# MSP430.net
KiCad netlist of a schematic drawn in Altium Designer
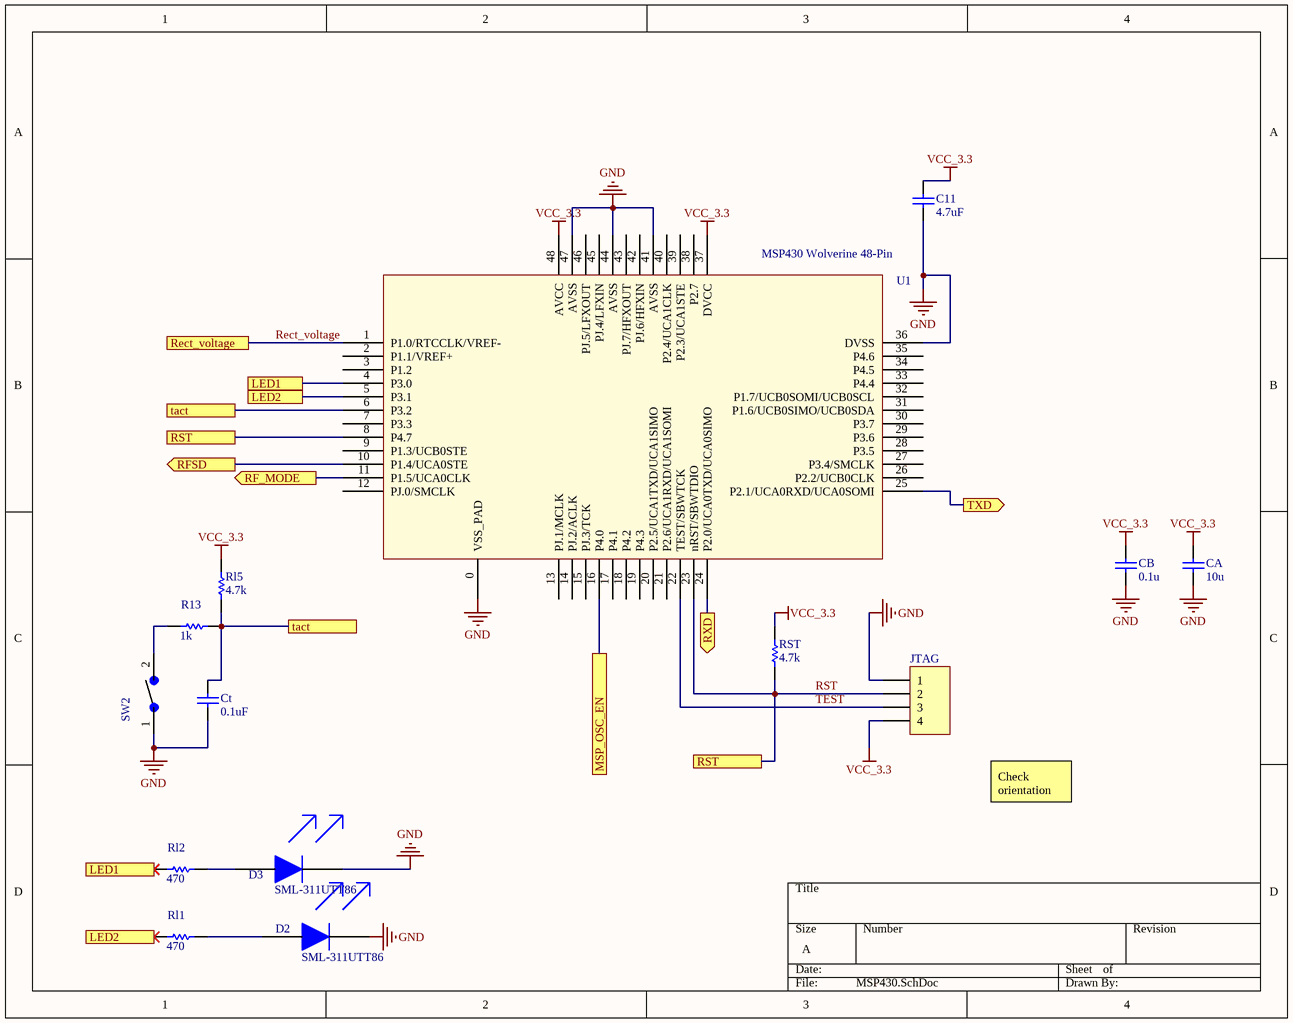
[diagram p0: MSP430.SchDoc]

(export (version "E")
  (design (tool "Eeschema 10.0.6"))
  (components
    (comp (ref "C11")
      (value "4.7uF")
      (footprint "0402-W")
      (description "Ceramic Capacitor (Surface Mount)")
      (fields (field (name "MANUFACTURER") "Generic Ceramic Chip Cap (TBD)") (field (name "Comment") "Cap"))
      (libsource (lib "WISP_AD10") (part "Cap"))
    )
    (comp (ref "CA")
      (value "10u")
      (footprint "0402-W")
      (description "Ceramic Capacitor (Surface Mount)")
      (fields (field (name "MANUFACTURER") "Generic Ceramic Chip Cap (TBD)") (field (name "Comment") "Cap"))
      (libsource (lib "wisp") (part "Cap"))
    )
    (comp (ref "CB")
      (value "0.1u")
      (footprint "0402-W")
      (description "Ceramic Capacitor (Surface Mount)")
      (fields (field (name "MANUFACTURER") "Generic Ceramic Chip Cap (TBD)") (field (name "Comment") "Cap"))
      (libsource (lib "wisp") (part "Cap"))
    )
    (comp (ref "Ct")
      (value "0.1uF")
      (footprint "0402-W")
      (description "Ceramic Capacitor (Surface Mount)")
      (fields (field (name "MANUFACTURER") "Generic Ceramic Chip Cap (TBD)") (field (name "Comment") "Cap"))
      (libsource (lib "WISP_AD10") (part "Cap"))
    )
    (comp (ref "D2")
      (value "SML-311UTT86")
      (footprint "0603")
      (description "LED 630NM RED WTR CLR 0603 SMD")
      (libsource (lib "Fromm") (part "SML-311UTT86"))
    )
    (comp (ref "D3")
      (value "SML-311UTT86")
      (footprint "0603")
      (description "LED 630NM RED WTR CLR 0603 SMD")
      (libsource (lib "Fromm") (part "SML-311UTT86"))
    )
    (comp (ref "JTAG")
      (value "MHDR1X4")
      (footprint "MHDR1X4")
      (description "Header, 4-Pin")
      (fields (field (name "PUBLISHER") "Altium Limited"))
      (libsource (lib "Miscellaneous Connectors") (part "MHDR1X4"))
    )
    (comp (ref "R13")
      (value "1k")
      (footprint "0402")
      (description "Chip Resistor (Surface Mount)")
      (fields (field (name "MANUFACTURER") "Generic Chip Res (TBD)") (field (name "Comment") "Res"))
      (libsource (lib "wisp") (part "Res"))
    )
    (comp (ref "Rl1")
      (value "470")
      (footprint "0402")
      (description "Chip Resistor (Surface Mount)")
      (fields (field (name "MANUFACTURER") "Generic Chip Res (TBD)") (field (name "Comment") "Res"))
      (libsource (lib "wisp") (part "Res"))
    )
    (comp (ref "Rl2")
      (value "470")
      (footprint "0402")
      (description "Chip Resistor (Surface Mount)")
      (fields (field (name "MANUFACTURER") "Generic Chip Res (TBD)") (field (name "Comment") "Res"))
      (libsource (lib "wisp") (part "Res"))
    )
    (comp (ref "Rl5")
      (value "4.7k")
      (footprint "0402")
      (description "Chip Resistor (Surface Mount)")
      (fields (field (name "MANUFACTURER") "Generic Chip Res (TBD)") (field (name "Comment") "Res"))
      (libsource (lib "wisp") (part "Res"))
    )
    (comp (ref "RST")
      (value "Res")
      (footprint "0402")
      (description "Chip Resistor (Surface Mount)")
      (fields (field (name "MANUFACTURER") "Generic Chip Res (TBD)") (field (name "RST") "4.7k"))
      (libsource (lib "wisp") (part "Res"))
    )
    (comp (ref "SW2")
      (value "FSMSM _1437566-3_")
      (footprint "TE_FSMSM")
      (description "FSMSM=3.5X6 SMT TACT")
      (fields (field (name "MF") "TE Connectivity") (field (name "MP") "FSMSM"))
      (libsource (lib "FSMSM") (part "FSMSM"))
    )
    (comp (ref "U1")
      (value "MSP430 Wolverine 48-Pin")
      (footprint "MSP_QFN48_RGZ_PAD0")
      (description "16-bit FRAM MCU")
      (libsource (lib "wisp") (part "MSP430FR596X_586X_RGZ"))
    )
  )
  (nets
    (net (code "1") (name "/LED1") (class "Default")
      (node (ref "Rl2") (pin "2") (pinfunction "2_2") (pintype "passive"))
      (node (ref "U1") (pin "4") (pinfunction "P3.0_4") (pintype "passive"))
    )
    (net (code "2") (name "/LED2") (class "Default")
      (node (ref "Rl1") (pin "2") (pinfunction "2_2") (pintype "passive"))
      (node (ref "U1") (pin "5") (pinfunction "P3.1_5") (pintype "passive"))
    )
    (net (code "3") (name "/MSP_OSC_EN") (class "Default")
      (node (ref "U1") (pin "16") (pinfunction "P4.0_16") (pintype "passive"))
    )
    (net (code "4") (name "/RFSD") (class "Default")
      (node (ref "U1") (pin "10") (pinfunction "P1.4/UCA0STE_10") (pintype "passive"))
    )
    (net (code "5") (name "/RF_MODE") (class "Default")
      (node (ref "U1") (pin "11") (pinfunction "P1.5/UCA0CLK_11") (pintype "passive"))
    )
    (net (code "6") (name "/RST") (class "Default")
      (node (ref "JTAG") (pin "2") (pinfunction "2_2") (pintype "passive"))
      (node (ref "RST") (pin "1") (pinfunction "1_1") (pintype "passive"))
      (node (ref "U1") (pin "23") (pinfunction "nRST/SBWTDIO_23") (pintype "passive"))
      (node (ref "U1") (pin "8") (pinfunction "P4.7_8") (pintype "passive"))
    )
    (net (code "7") (name "/RXD") (class "Default")
      (node (ref "U1") (pin "24") (pinfunction "P2.0/UCA0TXD/UCA0SIMO_24") (pintype "passive"))
    )
    (net (code "8") (name "/Rect_voltage") (class "Default")
      (node (ref "U1") (pin "1") (pinfunction "P1.0/RTCCLK/VREF-_1") (pintype "passive"))
    )
    (net (code "9") (name "/TEST") (class "Default")
      (node (ref "JTAG") (pin "3") (pinfunction "3_3") (pintype "passive"))
      (node (ref "U1") (pin "22") (pinfunction "TEST/SBWTCK_22") (pintype "passive"))
    )
    (net (code "10") (name "/TXD") (class "Default")
      (node (ref "U1") (pin "25") (pinfunction "P2.1/UCA0RXD/UCA0SOMI_25") (pintype "passive"))
    )
    (net (code "11") (name "/tact") (class "Default")
      (node (ref "Ct") (pin "2") (pinfunction "2_2") (pintype "passive"))
      (node (ref "R13") (pin "1") (pinfunction "1_1") (pintype "passive"))
      (node (ref "Rl5") (pin "2") (pinfunction "2_2") (pintype "passive"))
      (node (ref "U1") (pin "6") (pinfunction "P3.2_6") (pintype "passive"))
    )
    (net (code "12") (name "GND") (class "Default")
      (node (ref "C11") (pin "1") (pinfunction "1_1") (pintype "passive"))
      (node (ref "CA") (pin "1") (pinfunction "1_1") (pintype "passive"))
      (node (ref "CB") (pin "1") (pinfunction "1_1") (pintype "passive"))
      (node (ref "Ct") (pin "1") (pinfunction "1_1") (pintype "passive"))
      (node (ref "D2") (pin "2") (pintype "passive"))
      (node (ref "D3") (pin "2") (pintype "passive"))
      (node (ref "JTAG") (pin "1") (pinfunction "1_1") (pintype "passive"))
      (node (ref "SW2") (pin "1") (pinfunction "1_1") (pintype "passive"))
      (node (ref "U1") (pin "0") (pinfunction "VSS_PAD_0") (pintype "passive"))
      (node (ref "U1") (pin "36") (pinfunction "DVSS_36") (pintype "passive"))
      (node (ref "U1") (pin "41") (pinfunction "AVSS_41") (pintype "passive"))
      (node (ref "U1") (pin "44") (pinfunction "AVSS_44") (pintype "passive"))
      (node (ref "U1") (pin "47") (pinfunction "AVSS_47") (pintype "passive"))
    )
    (net (code "13") (name "Net-(D2-Pad1)") (class "Default")
      (node (ref "D2") (pin "1") (pintype "passive"))
      (node (ref "Rl1") (pin "1") (pinfunction "1_1") (pintype "passive"))
    )
    (net (code "14") (name "Net-(D3-Pad1)") (class "Default")
      (node (ref "D3") (pin "1") (pintype "passive"))
      (node (ref "Rl2") (pin "1") (pinfunction "1_1") (pintype "passive"))
    )
    (net (code "15") (name "Net-(R13-Pad2)") (class "Default")
      (node (ref "R13") (pin "2") (pinfunction "2_2") (pintype "passive"))
      (node (ref "SW2") (pin "2") (pinfunction "2_2") (pintype "passive"))
    )
    (net (code "16") (name "VCC_3.3") (class "Default")
      (node (ref "C11") (pin "2") (pinfunction "2_2") (pintype "passive"))
      (node (ref "CA") (pin "2") (pinfunction "2_2") (pintype "passive"))
      (node (ref "CB") (pin "2") (pinfunction "2_2") (pintype "passive"))
      (node (ref "JTAG") (pin "4") (pinfunction "4_4") (pintype "passive"))
      (node (ref "RST") (pin "2") (pinfunction "2_2") (pintype "passive"))
      (node (ref "Rl5") (pin "1") (pinfunction "1_1") (pintype "passive"))
      (node (ref "U1") (pin "37") (pinfunction "DVCC_37") (pintype "passive"))
      (node (ref "U1") (pin "48") (pinfunction "AVCC_48") (pintype "passive"))
    )
    (net (code "17") (name "unconnected-(U1-P1.1{slash}VREF+-Pad2)") (class "Default")
      (node (ref "U1") (pin "2") (pinfunction "P1.1/VREF+_2") (pintype "passive"))
    )
    (net (code "18") (name "unconnected-(U1-P1.2-Pad3)") (class "Default")
      (node (ref "U1") (pin "3") (pinfunction "P1.2_3") (pintype "passive"))
    )
    (net (code "19") (name "unconnected-(U1-P1.3{slash}UCB0STE-Pad9)") (class "Default")
      (node (ref "U1") (pin "9") (pinfunction "P1.3/UCB0STE_9") (pintype "passive"))
    )
    (net (code "20") (name "unconnected-(U1-P1.6{slash}UCB0SIMO{slash}UCB0SDA-Pad31)") (class "Default")
      (node (ref "U1") (pin "31") (pinfunction "P1.6/UCB0SIMO/UCB0SDA_31") (pintype "passive"))
    )
    (net (code "21") (name "unconnected-(U1-P1.7{slash}UCB0SOMI{slash}UCB0SCL-Pad32)") (class "Default")
      (node (ref "U1") (pin "32") (pinfunction "P1.7/UCB0SOMI/UCB0SCL_32") (pintype "passive"))
    )
    (net (code "22") (name "unconnected-(U1-P2.2{slash}UCB0CLK-Pad26)") (class "Default")
      (node (ref "U1") (pin "26") (pinfunction "P2.2/UCB0CLK_26") (pintype "passive"))
    )
    (net (code "23") (name "unconnected-(U1-P2.3{slash}UCA1STE-Pad39)") (class "Default")
      (node (ref "U1") (pin "39") (pinfunction "P2.3/UCA1STE_39") (pintype "passive"))
    )
    (net (code "24") (name "unconnected-(U1-P2.4{slash}UCA1CLK-Pad40)") (class "Default")
      (node (ref "U1") (pin "40") (pinfunction "P2.4/UCA1CLK_40") (pintype "passive"))
    )
    (net (code "25") (name "unconnected-(U1-P2.5{slash}UCA1TXD{slash}UCA1SIMO-Pad20)") (class "Default")
      (node (ref "U1") (pin "20") (pinfunction "P2.5/UCA1TXD/UCA1SIMO_20") (pintype "passive"))
    )
    (net (code "26") (name "unconnected-(U1-P2.6{slash}UCA1RXD{slash}UCA1SOMI-Pad21)") (class "Default")
      (node (ref "U1") (pin "21") (pinfunction "P2.6/UCA1RXD/UCA1SOMI_21") (pintype "passive"))
    )
    (net (code "27") (name "unconnected-(U1-P2.7-Pad38)") (class "Default")
      (node (ref "U1") (pin "38") (pinfunction "P2.7_38") (pintype "passive"))
    )
    (net (code "28") (name "unconnected-(U1-P3.3-Pad7)") (class "Default")
      (node (ref "U1") (pin "7") (pinfunction "P3.3_7") (pintype "passive"))
    )
    (net (code "29") (name "unconnected-(U1-P3.4{slash}SMCLK-Pad27)") (class "Default")
      (node (ref "U1") (pin "27") (pinfunction "P3.4/SMCLK_27") (pintype "passive"))
    )
    (net (code "30") (name "unconnected-(U1-P3.5-Pad28)") (class "Default")
      (node (ref "U1") (pin "28") (pinfunction "P3.5_28") (pintype "passive"))
    )
    (net (code "31") (name "unconnected-(U1-P3.6-Pad29)") (class "Default")
      (node (ref "U1") (pin "29") (pinfunction "P3.6_29") (pintype "passive"))
    )
    (net (code "32") (name "unconnected-(U1-P3.7-Pad30)") (class "Default")
      (node (ref "U1") (pin "30") (pinfunction "P3.7_30") (pintype "passive"))
    )
    (net (code "33") (name "unconnected-(U1-P4.1-Pad17)") (class "Default")
      (node (ref "U1") (pin "17") (pinfunction "P4.1_17") (pintype "passive"))
    )
    (net (code "34") (name "unconnected-(U1-P4.2-Pad18)") (class "Default")
      (node (ref "U1") (pin "18") (pinfunction "P4.2_18") (pintype "passive"))
    )
    (net (code "35") (name "unconnected-(U1-P4.3-Pad19)") (class "Default")
      (node (ref "U1") (pin "19") (pinfunction "P4.3_19") (pintype "passive"))
    )
    (net (code "36") (name "unconnected-(U1-P4.4-Pad33)") (class "Default")
      (node (ref "U1") (pin "33") (pinfunction "P4.4_33") (pintype "passive"))
    )
    (net (code "37") (name "unconnected-(U1-P4.5-Pad34)") (class "Default")
      (node (ref "U1") (pin "34") (pinfunction "P4.5_34") (pintype "passive"))
    )
    (net (code "38") (name "unconnected-(U1-P4.6-Pad35)") (class "Default")
      (node (ref "U1") (pin "35") (pinfunction "P4.6_35") (pintype "passive"))
    )
    (net (code "39") (name "unconnected-(U1-PJ.0{slash}SMCLK-Pad12)") (class "Default")
      (node (ref "U1") (pin "12") (pinfunction "PJ.0/SMCLK_12") (pintype "passive"))
    )
    (net (code "40") (name "unconnected-(U1-PJ.1{slash}MCLK-Pad13)") (class "Default")
      (node (ref "U1") (pin "13") (pinfunction "PJ.1/MCLK_13") (pintype "passive"))
    )
    (net (code "41") (name "unconnected-(U1-PJ.2{slash}ACLK-Pad14)") (class "Default")
      (node (ref "U1") (pin "14") (pinfunction "PJ.2/ACLK_14") (pintype "passive"))
    )
    (net (code "42") (name "unconnected-(U1-PJ.3{slash}TCK-Pad15)") (class "Default")
      (node (ref "U1") (pin "15") (pinfunction "PJ.3/TCK_15") (pintype "passive"))
    )
    (net (code "43") (name "unconnected-(U1-PJ.4{slash}LFXIN-Pad45)") (class "Default")
      (node (ref "U1") (pin "45") (pinfunction "PJ.4/LFXIN_45") (pintype "passive"))
    )
    (net (code "44") (name "unconnected-(U1-PJ.5{slash}LFXOUT-Pad46)") (class "Default")
      (node (ref "U1") (pin "46") (pinfunction "PJ.5/LFXOUT_46") (pintype "passive"))
    )
    (net (code "45") (name "unconnected-(U1-PJ.6{slash}HFXIN-Pad42)") (class "Default")
      (node (ref "U1") (pin "42") (pinfunction "PJ.6/HFXIN_42") (pintype "passive"))
    )
    (net (code "46") (name "unconnected-(U1-PJ.7{slash}HFXOUT-Pad43)") (class "Default")
      (node (ref "U1") (pin "43") (pinfunction "PJ.7/HFXOUT_43") (pintype "passive"))
    )
  )
)
